# main.net
KiCad netlist of a schematic drawn in EAGLE
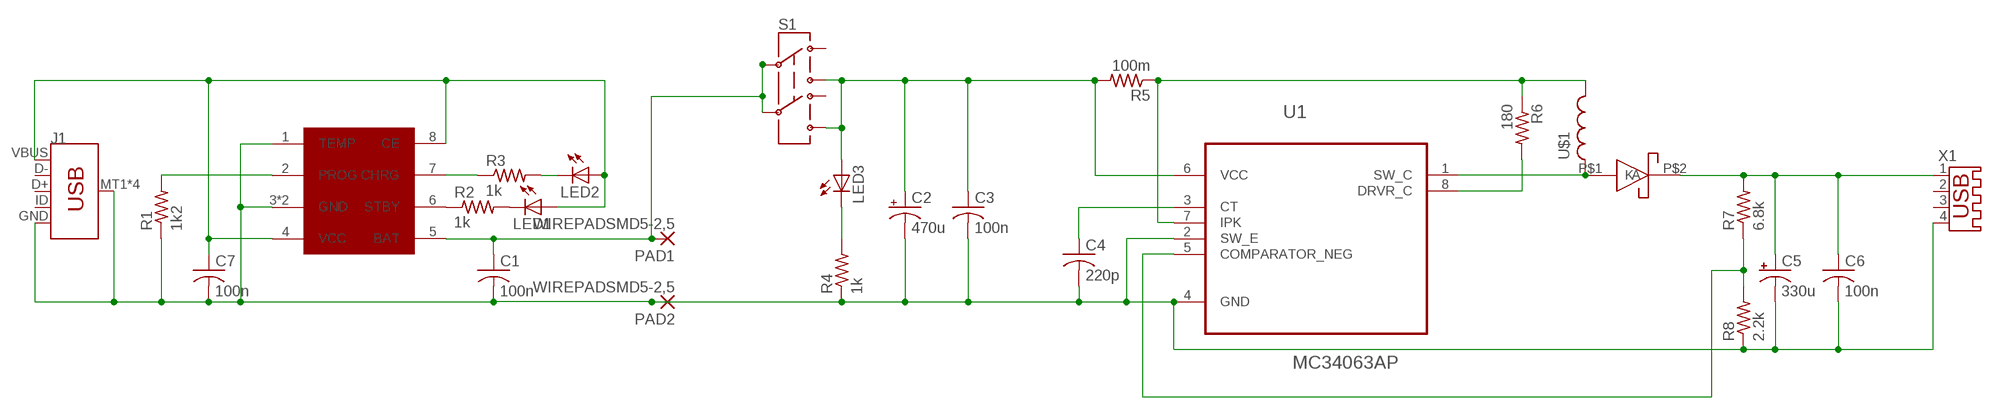
[diagram p0: schematic, sheet 1]

(export (version "E")
  (design (tool "Eeschema 10.0.6"))
  (components
    (comp (ref "C1")
      (value "100n")
      (footprint "eagle-import:C0603")
      (libsource (lib "eagle-import") (part "C-USC0603"))
    )
    (comp (ref "C2")
      (value "470u")
      (footprint "eagle-import:E5-10,5")
      (libsource (lib "eagle-import") (part "CPOL-USE5-10.5"))
    )
    (comp (ref "C3")
      (value "100n")
      (footprint "eagle-import:C0603")
      (libsource (lib "eagle-import") (part "C-USC0603"))
    )
    (comp (ref "C4")
      (value "220p")
      (footprint "eagle-import:C025-025X050")
      (libsource (lib "eagle-import") (part "C-US025-025X050"))
    )
    (comp (ref "C5")
      (value "330u")
      (footprint "eagle-import:E3,5-8")
      (libsource (lib "eagle-import") (part "CPOL-USE3.5-8"))
    )
    (comp (ref "C6")
      (value "100n")
      (footprint "eagle-import:C0603")
      (libsource (lib "eagle-import") (part "C-USC0603"))
    )
    (comp (ref "C7")
      (value "100n")
      (footprint "eagle-import:C0603")
      (libsource (lib "eagle-import") (part "C-USC0603"))
    )
    (comp (ref "CH1")
      (value "TP4056")
      (footprint "eagle-import:SOP8")
      (libsource (lib "eagle-import") (part "TP4056"))
    )
    (comp (ref "D1")
      (value "SS34")
      (footprint "eagle-import:DO-214AB")
      (libsource (lib "eagle-import") (part "SS34"))
    )
    (comp (ref "J1")
      (value "USB_MICRO-B_SMT")
      (footprint "eagle-import:USB-MICROB")
      (libsource (lib "eagle-import") (part "USB_MICRO-B_SMT"))
    )
    (comp (ref "LED1")
      (value "LEDCHIP-LED0805")
      (footprint "eagle-import:CHIP-LED0805")
      (libsource (lib "eagle-import") (part "LEDCHIP-LED0805"))
    )
    (comp (ref "LED2")
      (value "LEDCHIP-LED0805")
      (footprint "eagle-import:CHIP-LED0805")
      (libsource (lib "eagle-import") (part "LEDCHIP-LED0805"))
    )
    (comp (ref "LED3")
      (value "LEDCHIP-LED0805")
      (footprint "eagle-import:CHIP-LED0805")
      (libsource (lib "eagle-import") (part "LEDCHIP-LED0805"))
    )
    (comp (ref "PAD1")
      (value "WIREPADSMD5-2,5")
      (footprint "eagle-import:5-2,5")
      (libsource (lib "eagle-import") (part "WIREPADSMD5-2,5"))
    )
    (comp (ref "PAD2")
      (value "WIREPADSMD5-2,5")
      (footprint "eagle-import:5-2,5")
      (libsource (lib "eagle-import") (part "WIREPADSMD5-2,5"))
    )
    (comp (ref "R1")
      (value "1k2")
      (footprint "eagle-import:M0805")
      (libsource (lib "eagle-import") (part "R-US_M0805"))
    )
    (comp (ref "R2")
      (value "1k")
      (footprint "eagle-import:M0805")
      (libsource (lib "eagle-import") (part "R-US_M0805"))
    )
    (comp (ref "R3")
      (value "1k")
      (footprint "eagle-import:M0805")
      (libsource (lib "eagle-import") (part "R-US_M0805"))
    )
    (comp (ref "R4")
      (value "1k")
      (footprint "eagle-import:M0805")
      (libsource (lib "eagle-import") (part "R-US_M0805"))
    )
    (comp (ref "R5")
      (value "100m")
      (footprint "eagle-import:R0603")
      (libsource (lib "eagle-import") (part "R-US_R0603"))
    )
    (comp (ref "R6")
      (value "180")
      (footprint "eagle-import:0309V")
      (libsource (lib "eagle-import") (part "R-US_0309/V"))
    )
    (comp (ref "R7")
      (value "6.8k")
      (footprint "eagle-import:0204_5")
      (libsource (lib "eagle-import") (part "R-US_0204/5"))
    )
    (comp (ref "R8")
      (value "2.2k")
      (footprint "eagle-import:M0805")
      (libsource (lib "eagle-import") (part "R-US_M0805"))
    )
    (comp (ref "S1")
      (value "SWITCH-DPDTEG2211")
      (footprint "eagle-import:EG2211")
      (libsource (lib "eagle-import") (part "SWITCH-DPDTEG2211"))
    )
    (comp (ref "U$1")
      (value "DO540H")
      (footprint "eagle-import:DO540H")
      (libsource (lib "eagle-import") (part "DO540H"))
    )
    (comp (ref "U1")
      (value "MC34063AP")
      (footprint "eagle-import:DIP254P762X508-8")
      (libsource (lib "eagle-import") (part "MC34063AP"))
    )
    (comp (ref "X1")
      (value "USB-A003")
      (footprint "eagle-import:USB-A003")
      (libsource (lib "eagle-import") (part "USB-A003"))
    )
  )
  (nets
    (net (code "1") (name "Net-(CH1-BAT)") (class "Default")
      (node (ref "C1") (pin "1") (pinfunction "1_1") (pintype "passive"))
      (node (ref "CH1") (pin "5") (pinfunction "BAT_5") (pintype "bidirectional"))
      (node (ref "PAD1") (pin "1") (pinfunction "P_1") (pintype "passive"))
      (node (ref "S1") (pin "P1") (pinfunction "2_P1") (pintype "bidirectional"))
      (node (ref "S1") (pin "P2") (pinfunction "5_P2") (pintype "bidirectional"))
    )
    (net (code "2") (name "Net-(CH1-CE)") (class "Default")
      (node (ref "C7") (pin "1") (pinfunction "1_1") (pintype "passive"))
      (node (ref "CH1") (pin "4") (pinfunction "VCC_4") (pintype "bidirectional"))
      (node (ref "CH1") (pin "8") (pinfunction "CE_8") (pintype "bidirectional"))
      (node (ref "J1") (pin "VBUS") (pinfunction "VBUS_VBUS") (pintype "power_in"))
      (node (ref "LED1") (pin "A") (pinfunction "A_A") (pintype "passive"))
      (node (ref "LED2") (pin "A") (pinfunction "A_A") (pintype "passive"))
    )
    (net (code "3") (name "Net-(CH1-CHRG)") (class "Default")
      (node (ref "CH1") (pin "7") (pinfunction "CHRG_7") (pintype "bidirectional"))
      (node (ref "R3") (pin "1") (pinfunction "1_1") (pintype "passive"))
    )
    (net (code "4") (name "Net-(CH1-PROG)") (class "Default")
      (node (ref "CH1") (pin "2") (pinfunction "PROG_2") (pintype "bidirectional"))
      (node (ref "R1") (pin "2") (pinfunction "2_2") (pintype "passive"))
    )
    (net (code "5") (name "Net-(CH1-STBY)") (class "Default")
      (node (ref "CH1") (pin "6") (pinfunction "STBY_6") (pintype "bidirectional"))
      (node (ref "R2") (pin "1") (pinfunction "1_1") (pintype "passive"))
    )
    (net (code "6") (name "Net-(CH1-TEMP)") (class "Default")
      (node (ref "C1") (pin "2") (pinfunction "2_2") (pintype "passive"))
      (node (ref "C2") (pin "-") (pinfunction "-_-") (pintype "passive"))
      (node (ref "C3") (pin "2") (pinfunction "2_2") (pintype "passive"))
      (node (ref "C4") (pin "2") (pinfunction "2_2") (pintype "passive"))
      (node (ref "C5") (pin "-") (pinfunction "-_-") (pintype "passive"))
      (node (ref "C6") (pin "2") (pinfunction "2_2") (pintype "passive"))
      (node (ref "C7") (pin "2") (pinfunction "2_2") (pintype "passive"))
      (node (ref "CH1") (pin "1") (pinfunction "TEMP_1") (pintype "bidirectional"))
      (node (ref "CH1") (pin "3") (pinfunction "GND_3") (pintype "bidirectional"))
      (node (ref "CH1") (pin "9") (pinfunction "GND_9") (pintype "bidirectional"))
      (node (ref "J1") (pin "GND") (pinfunction "GND_GND") (pintype "power_in"))
      (node (ref "J1") (pin "MT1") (pinfunction "SHIELD_MT1") (pintype "bidirectional"))
      (node (ref "J1") (pin "MT2") (pinfunction "SHIELD_MT2") (pintype "bidirectional"))
      (node (ref "J1") (pin "P$1") (pinfunction "SHIELD_P$1") (pintype "bidirectional"))
      (node (ref "J1") (pin "P$2") (pinfunction "SHIELD_P$2") (pintype "bidirectional"))
      (node (ref "PAD2") (pin "1") (pinfunction "P_1") (pintype "passive"))
      (node (ref "R1") (pin "1") (pinfunction "1_1") (pintype "passive"))
      (node (ref "R4") (pin "1") (pinfunction "1_1") (pintype "passive"))
      (node (ref "R8") (pin "1") (pinfunction "1_1") (pintype "passive"))
      (node (ref "U1") (pin "2") (pinfunction "SW_E_2") (pintype "input"))
      (node (ref "U1") (pin "4") (pinfunction "GND_4") (pintype "passive"))
      (node (ref "X1") (pin "4") (pinfunction "4_4") (pintype "passive"))
    )
    (net (code "7") (name "Net-(D1-A)") (class "Default")
      (node (ref "D1") (pin "P$1") (pinfunction "A_P$1") (pintype "bidirectional"))
      (node (ref "U$1") (pin "P$2") (pinfunction "P$2_P$2") (pintype "passive"))
      (node (ref "U1") (pin "1") (pinfunction "SW_C_1") (pintype "passive"))
    )
    (net (code "8") (name "Net-(D1-K)") (class "Default")
      (node (ref "C5") (pin "+") (pinfunction "+_+") (pintype "passive"))
      (node (ref "C6") (pin "1") (pinfunction "1_1") (pintype "passive"))
      (node (ref "D1") (pin "P$2") (pinfunction "K_P$2") (pintype "bidirectional"))
      (node (ref "R7") (pin "2") (pinfunction "2_2") (pintype "passive"))
      (node (ref "X1") (pin "1") (pinfunction "1_1") (pintype "passive"))
    )
    (net (code "9") (name "Net-(LED1-PadC)") (class "Default")
      (node (ref "LED1") (pin "C") (pinfunction "C_C") (pintype "passive"))
      (node (ref "R2") (pin "2") (pinfunction "2_2") (pintype "passive"))
    )
    (net (code "10") (name "Net-(LED2-PadC)") (class "Default")
      (node (ref "LED2") (pin "C") (pinfunction "C_C") (pintype "passive"))
      (node (ref "R3") (pin "2") (pinfunction "2_2") (pintype "passive"))
    )
    (net (code "11") (name "Net-(LED3-PadC)") (class "Default")
      (node (ref "LED3") (pin "C") (pinfunction "C_C") (pintype "passive"))
      (node (ref "R4") (pin "2") (pinfunction "2_2") (pintype "passive"))
    )
    (net (code "12") (name "Net-(S1-3)") (class "Default")
      (node (ref "C2") (pin "+") (pinfunction "+_+") (pintype "passive"))
      (node (ref "C3") (pin "1") (pinfunction "1_1") (pintype "passive"))
      (node (ref "LED3") (pin "A") (pinfunction "A_A") (pintype "passive"))
      (node (ref "R5") (pin "2") (pinfunction "2_2") (pintype "passive"))
      (node (ref "S1") (pin "P1-TB") (pinfunction "3_P1-TB") (pintype "bidirectional"))
      (node (ref "S1") (pin "P2-TB") (pinfunction "6_P2-TB") (pintype "bidirectional"))
      (node (ref "U1") (pin "6") (pinfunction "VCC_6") (pintype "power_in"))
    )
    (net (code "13") (name "Net-(U1-COMPARATOR_NEG)") (class "Default")
      (node (ref "R7") (pin "1") (pinfunction "1_1") (pintype "passive"))
      (node (ref "R8") (pin "2") (pinfunction "2_2") (pintype "passive"))
      (node (ref "U1") (pin "5") (pinfunction "COMPARATOR_NEG_5") (pintype "input"))
    )
    (net (code "14") (name "Net-(U1-CT)") (class "Default")
      (node (ref "C4") (pin "1") (pinfunction "1_1") (pintype "passive"))
      (node (ref "U1") (pin "3") (pinfunction "CT_3") (pintype "input"))
    )
    (net (code "15") (name "Net-(U1-DRVR_C)") (class "Default")
      (node (ref "R6") (pin "2") (pinfunction "2_2") (pintype "passive"))
      (node (ref "U1") (pin "8") (pinfunction "DRVR_C_8") (pintype "passive"))
    )
    (net (code "16") (name "Net-(U1-IPK)") (class "Default")
      (node (ref "R5") (pin "1") (pinfunction "1_1") (pintype "passive"))
      (node (ref "R6") (pin "1") (pinfunction "1_1") (pintype "passive"))
      (node (ref "U$1") (pin "P$1") (pinfunction "P$1_P$1") (pintype "passive"))
      (node (ref "U1") (pin "7") (pinfunction "IPK_7") (pintype "input"))
    )
    (net (code "17") (name "unconnected-(J1-PadD+)") (class "Default")
      (node (ref "J1") (pin "D+") (pinfunction "D+_D+") (pintype "bidirectional"))
    )
    (net (code "18") (name "unconnected-(J1-PadD-)") (class "Default")
      (node (ref "J1") (pin "D-") (pinfunction "D-_D-") (pintype "bidirectional"))
    )
    (net (code "19") (name "unconnected-(J1-PadID)") (class "Default")
      (node (ref "J1") (pin "ID") (pinfunction "ID_ID") (pintype "bidirectional"))
    )
    (net (code "20") (name "unconnected-(S1-1-PadP1-TA)") (class "Default")
      (node (ref "S1") (pin "P1-TA") (pinfunction "1_P1-TA") (pintype "bidirectional"))
    )
    (net (code "21") (name "unconnected-(S1-4-PadP2-TA)") (class "Default")
      (node (ref "S1") (pin "P2-TA") (pinfunction "4_P2-TA") (pintype "bidirectional"))
    )
    (net (code "22") (name "unconnected-(X1-Pad2)") (class "Default")
      (node (ref "X1") (pin "2") (pinfunction "2_2") (pintype "passive"))
    )
    (net (code "23") (name "unconnected-(X1-Pad3)") (class "Default")
      (node (ref "X1") (pin "3") (pinfunction "3_3") (pintype "passive"))
    )
  )
)
